# IR_detector_16ch.net
KiCad netlist of a schematic drawn in Altium Designer
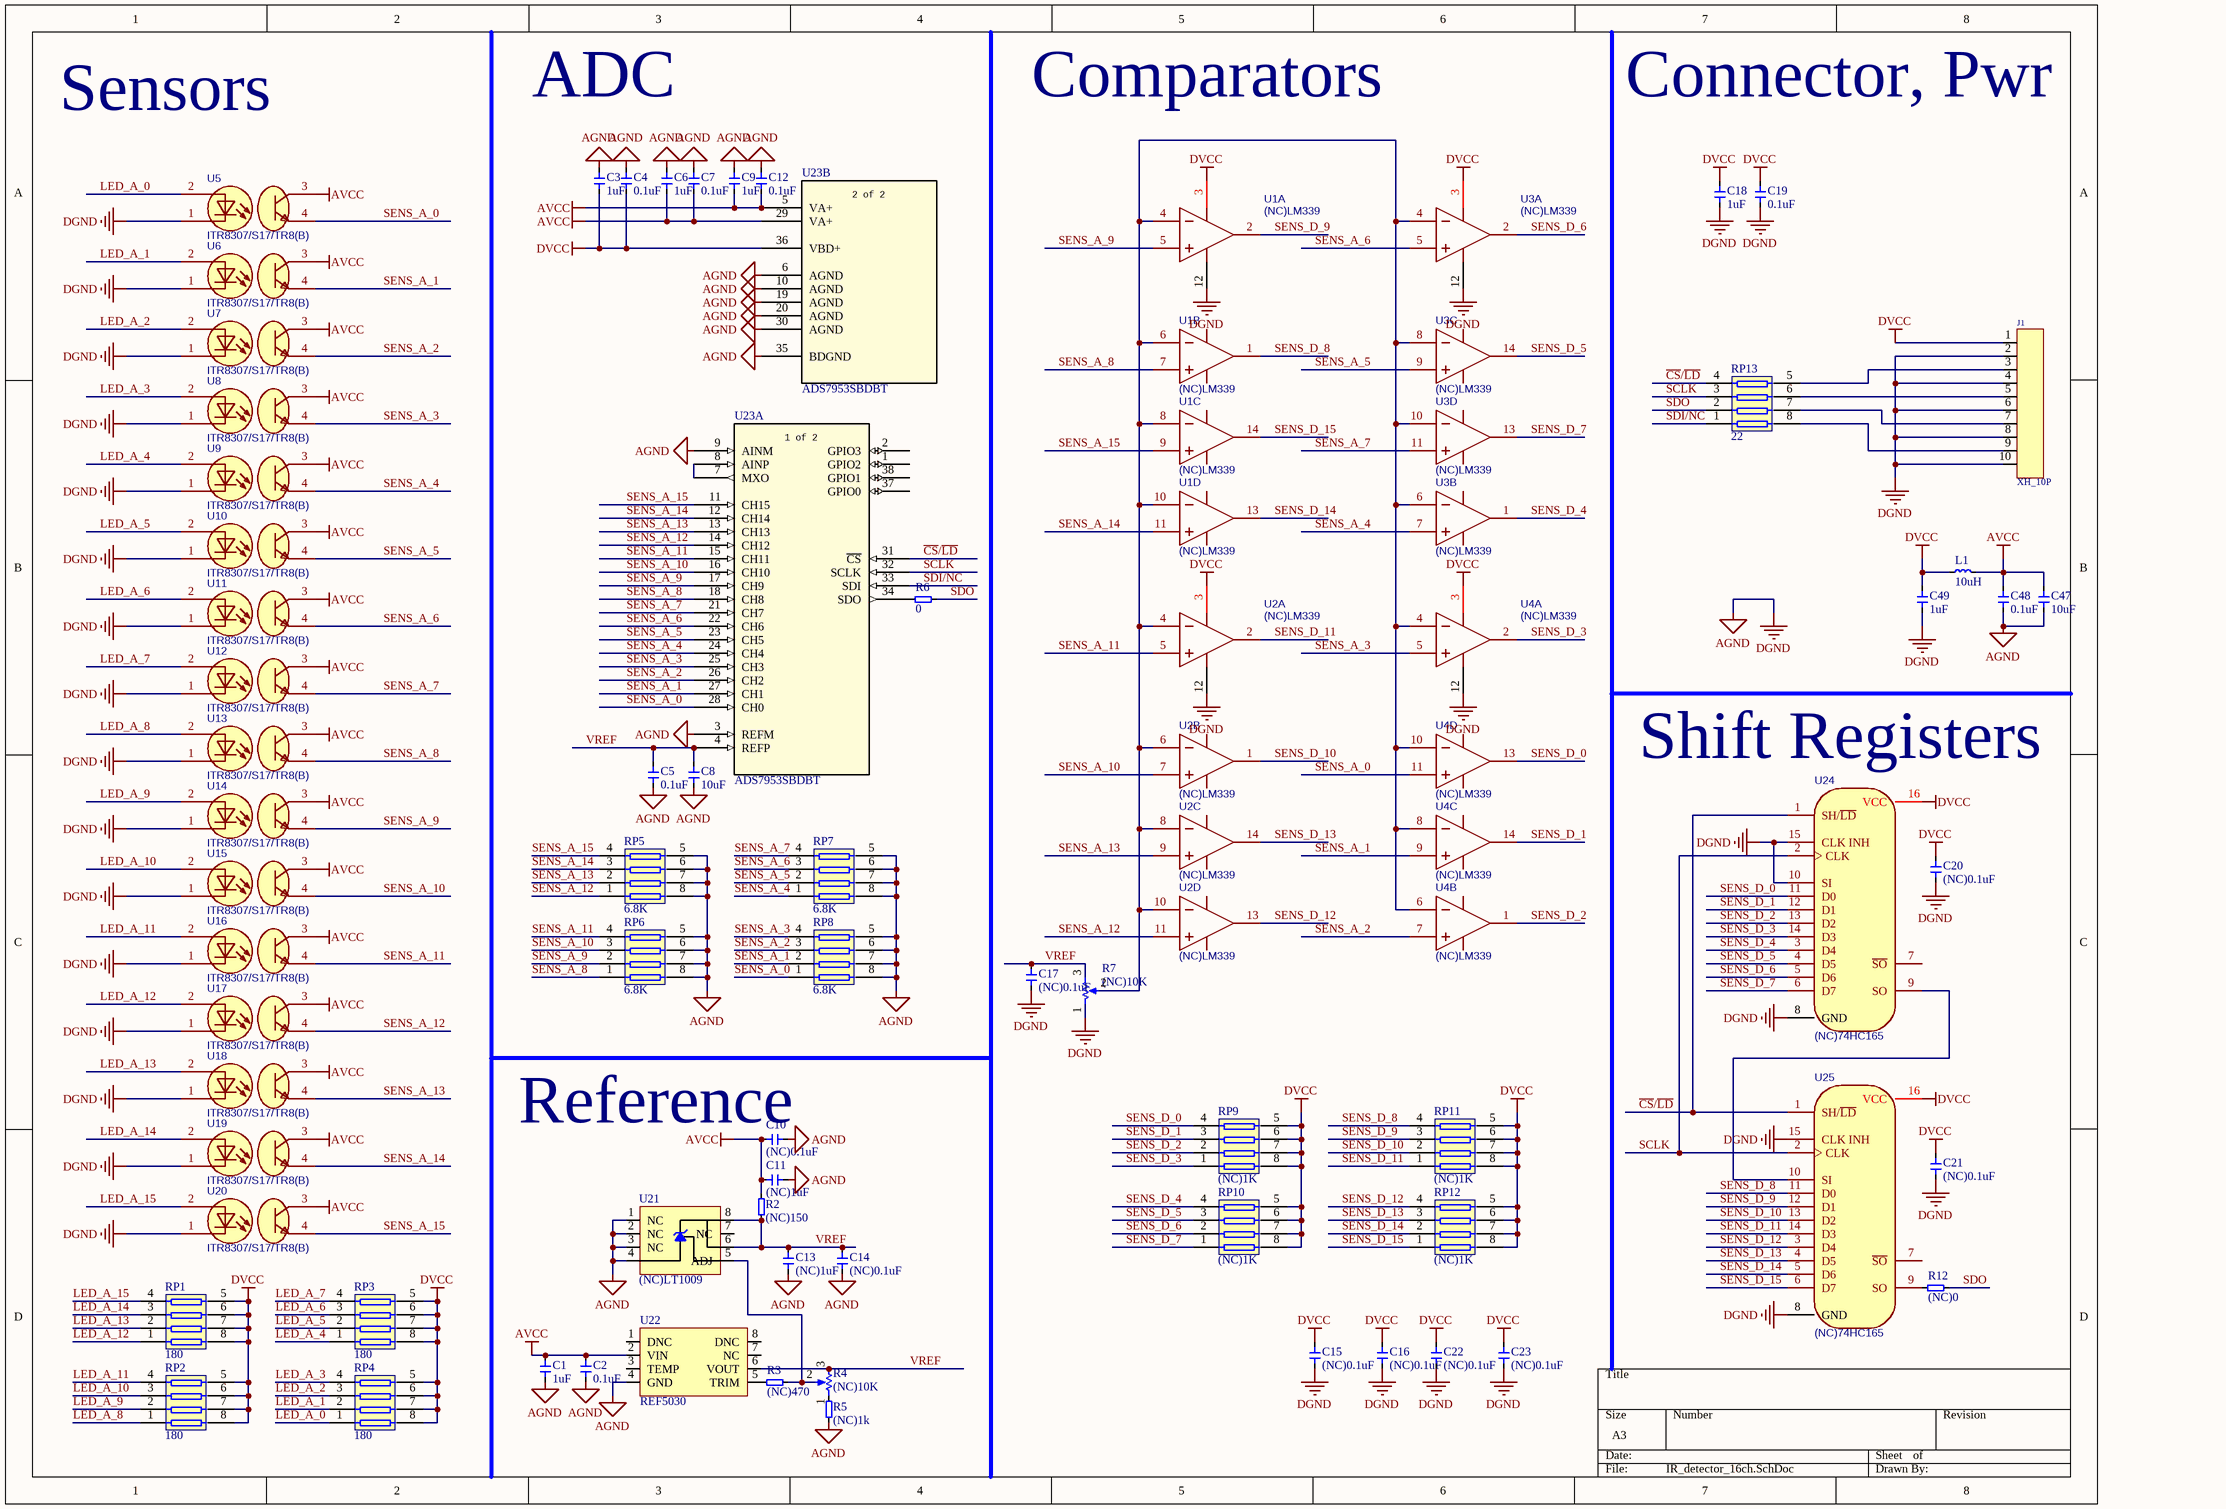
[diagram p0: IR_detector_16ch.SchDoc]

(export (version "E")
  (design (tool "Eeschema 10.0.6"))
  (components
    (comp (ref "C1") (value "1uF") (footprint "0402") (libsource (lib "pants1") (part "Cap")))
    (comp (ref "C2") (value "0.1uF") (footprint "0402") (libsource (lib "pants1") (part "Cap")))
    (comp (ref "C3") (value "1uF") (footprint "0402") (libsource (lib "pants1") (part "Cap")))
    (comp (ref "C4") (value "0.1uF") (footprint "0402") (libsource (lib "pants1") (part "Cap")))
    (comp (ref "C5") (value "0.1uF") (footprint "0402") (libsource (lib "pants1") (part "Cap")))
    (comp (ref "C6") (value "1uF") (footprint "0402") (libsource (lib "pants1") (part "Cap")))
    (comp (ref "C7") (value "0.1uF") (footprint "0402") (libsource (lib "pants1") (part "Cap")))
    (comp (ref "C8") (value "10uF") (footprint "0402") (libsource (lib "pants1") (part "Cap")))
    (comp (ref "C9") (value "1uF") (footprint "0402") (libsource (lib "pants1") (part "Cap")))
    (comp (ref "C10") (value "(NC)0.1uF") (footprint "0402") (libsource (lib "pants1") (part "Cap")))
    (comp (ref "C11") (value "(NC)1uF") (footprint "0402") (libsource (lib "pants1") (part "Cap")))
    (comp (ref "C12") (value "0.1uF") (footprint "0402") (libsource (lib "pants1") (part "Cap")))
    (comp (ref "C13") (value "(NC)1uF") (footprint "0402") (libsource (lib "pants1") (part "Cap")))
    (comp (ref "C14") (value "(NC)0.1uF") (footprint "0402") (libsource (lib "pants1") (part "Cap")))
    (comp (ref "C15") (value "(NC)0.1uF") (footprint "0402") (libsource (lib "pants1") (part "Cap")))
    (comp (ref "C16") (value "(NC)0.1uF") (footprint "0402") (libsource (lib "pants1") (part "Cap")))
    (comp (ref "C17") (value "(NC)0.1uF") (footprint "0402") (libsource (lib "pants1") (part "Cap")))
    (comp (ref "C18") (value "1uF") (footprint "0402") (libsource (lib "pants1") (part "Cap")))
    (comp (ref "C19") (value "0.1uF") (footprint "0402") (libsource (lib "pants1") (part "Cap")))
    (comp (ref "C20") (value "(NC)0.1uF") (footprint "0402") (libsource (lib "pants1") (part "Cap")))
    (comp (ref "C21") (value "(NC)0.1uF") (footprint "0402") (libsource (lib "pants1") (part "Cap")))
    (comp (ref "C22") (value "(NC)0.1uF") (footprint "0402") (libsource (lib "pants1") (part "Cap")))
    (comp (ref "C23") (value "(NC)0.1uF") (footprint "0402") (libsource (lib "pants1") (part "Cap")))
    (comp (ref "C47") (value "10uF") (footprint "0402") (libsource (lib "pants1") (part "Cap")))
    (comp (ref "C48") (value "0.1uF") (footprint "0402") (libsource (lib "pants1") (part "Cap")))
    (comp (ref "C49") (value "1uF") (footprint "0402") (libsource (lib "pants1") (part "Cap")))
    (comp (ref "J1")
      (value "XH_10P")
      (footprint "XH_10P直插弯针")
      (libsource (lib "XH_Connectors") (part "XH_10P"))
    )
    (comp (ref "L1")
      (value "10uH")
      (footprint "0603")
      (description "Inductor")
      (libsource (lib "pants1") (part "Inductor"))
    )
    (comp (ref "R2")
      (value "(NC)150")
      (footprint "0402")
      (description "Resistor")
      (libsource (lib "") (part "Res_1"))
    )
    (comp (ref "R3")
      (value "(NC)470")
      (footprint "0402")
      (description "Resistor")
      (libsource (lib "pants1") (part "Res"))
    )
    (comp (ref "R4") (value "(NC)10K") (footprint "3x3_ResPot") (libsource (lib "pants1") (part "ResPot")))
    (comp (ref "R5")
      (value "(NC)1k")
      (footprint "0402")
      (description "Resistor")
      (libsource (lib "") (part "Res_1"))
    )
    (comp (ref "R6")
      (value "0")
      (footprint "0402")
      (description "Resistor")
      (libsource (lib "pants1") (part "Res"))
    )
    (comp (ref "R7")
      (value "(NC)10K")
      (footprint "3362W-TH_3P-L7.1-W6.9-P2.54-BL-BS")
      (libsource (lib "pants1") (part "ResPot"))
    )
    (comp (ref "R12")
      (value "(NC)0")
      (footprint "0402")
      (description "Resistor")
      (libsource (lib "pants1") (part "Res"))
    )
    (comp (ref "RP1") (value "180") (footprint "8P4R-0603") (libsource (lib "pants1") (part "8P4R_F")))
    (comp (ref "RP2") (value "180") (footprint "8P4R-0603") (libsource (lib "pants1") (part "8P4R_F")))
    (comp (ref "RP3") (value "180") (footprint "8P4R-0603") (libsource (lib "pants1") (part "8P4R_F")))
    (comp (ref "RP4") (value "180") (footprint "8P4R-0603") (libsource (lib "pants1") (part "8P4R_F")))
    (comp (ref "RP5") (value "6.8K") (footprint "8P4R-0603") (libsource (lib "pants1") (part "8P4R_F")))
    (comp (ref "RP6") (value "6.8K") (footprint "8P4R-0603") (libsource (lib "pants1") (part "8P4R_F")))
    (comp (ref "RP7") (value "6.8K") (footprint "8P4R-0603") (libsource (lib "pants1") (part "8P4R_F")))
    (comp (ref "RP8") (value "6.8K") (footprint "8P4R-0603") (libsource (lib "pants1") (part "8P4R_F")))
    (comp (ref "RP9") (value "(NC)1K") (footprint "8P4R-0603") (libsource (lib "pants1") (part "8P4R_F")))
    (comp (ref "RP10") (value "(NC)1K") (footprint "8P4R-0603") (libsource (lib "pants1") (part "8P4R_F")))
    (comp (ref "RP11") (value "(NC)1K") (footprint "8P4R-0603") (libsource (lib "pants1") (part "8P4R_F")))
    (comp (ref "RP12") (value "(NC)1K") (footprint "8P4R-0603") (libsource (lib "pants1") (part "8P4R_F")))
    (comp (ref "RP13") (value "22") (footprint "8P4R-0603") (libsource (lib "pants1") (part "8P4R_F")))
    (comp (ref "U1")
      (value "(NC)LM339")
      (footprint "SOP-14_L8.6-W3.9-P1.27-LS6.0-BL")
      (fields
        (field (name "BOM_SUPPLIER PART") "C431330")
        (field (name "BOM_MANUFACTURER PART") "LM339-SR")
        (field (name "SUBPART_NO") "1")
      )
      (libsource (lib "pants1") (part "LM339"))
    )
    (comp (ref "U2")
      (value "(NC)LM339")
      (footprint "SOP-14_L8.6-W3.9-P1.27-LS6.0-BL")
      (fields
        (field (name "BOM_SUPPLIER PART") "C431330")
        (field (name "BOM_MANUFACTURER PART") "LM339-SR")
        (field (name "SUBPART_NO") "1")
      )
      (libsource (lib "pants1") (part "LM339"))
    )
    (comp (ref "U3")
      (value "(NC)LM339")
      (footprint "SOP-14_L8.6-W3.9-P1.27-LS6.0-BL")
      (fields
        (field (name "BOM_SUPPLIER PART") "C431330")
        (field (name "BOM_MANUFACTURER PART") "LM339-SR")
        (field (name "SUBPART_NO") "1")
      )
      (libsource (lib "pants1") (part "LM339"))
    )
    (comp (ref "U4")
      (value "(NC)LM339")
      (footprint "SOP-14_L8.6-W3.9-P1.27-LS6.0-BL")
      (fields
        (field (name "BOM_SUPPLIER PART") "C431330")
        (field (name "BOM_MANUFACTURER PART") "LM339-SR")
        (field (name "SUBPART_NO") "1")
      )
      (libsource (lib "pants1") (part "LM339"))
    )
    (comp (ref "U5")
      (value "ITR8307/S17/TR8(B)")
      (footprint "OPTO-SMD_ITR8307-S17-TR8-B-TS")
      (fields (field (name "BOM_SUPPLIER PART") "C81632"))
      (libsource (lib "pants1") (part "ITR8307/S17/TR8(B)"))
    )
    (comp (ref "U6")
      (value "ITR8307/S17/TR8(B)")
      (footprint "OPTO-SMD_ITR8307-S17-TR8-B-TS")
      (fields (field (name "BOM_SUPPLIER PART") "C81632"))
      (libsource (lib "pants1") (part "ITR8307/S17/TR8(B)"))
    )
    (comp (ref "U7")
      (value "ITR8307/S17/TR8(B)")
      (footprint "OPTO-SMD_ITR8307-S17-TR8-B-TS")
      (fields (field (name "BOM_SUPPLIER PART") "C81632"))
      (libsource (lib "pants1") (part "ITR8307/S17/TR8(B)"))
    )
    (comp (ref "U8")
      (value "ITR8307/S17/TR8(B)")
      (footprint "OPTO-SMD_ITR8307-S17-TR8-B-TS")
      (fields (field (name "BOM_SUPPLIER PART") "C81632"))
      (libsource (lib "pants1") (part "ITR8307/S17/TR8(B)"))
    )
    (comp (ref "U9")
      (value "ITR8307/S17/TR8(B)")
      (footprint "OPTO-SMD_ITR8307-S17-TR8-B-TS")
      (fields (field (name "BOM_SUPPLIER PART") "C81632"))
      (libsource (lib "pants1") (part "ITR8307/S17/TR8(B)"))
    )
    (comp (ref "U10")
      (value "ITR8307/S17/TR8(B)")
      (footprint "OPTO-SMD_ITR8307-S17-TR8-B-TS")
      (fields (field (name "BOM_SUPPLIER PART") "C81632"))
      (libsource (lib "pants1") (part "ITR8307/S17/TR8(B)"))
    )
    (comp (ref "U11")
      (value "ITR8307/S17/TR8(B)")
      (footprint "OPTO-SMD_ITR8307-S17-TR8-B-TS")
      (fields (field (name "BOM_SUPPLIER PART") "C81632"))
      (libsource (lib "pants1") (part "ITR8307/S17/TR8(B)"))
    )
    (comp (ref "U12")
      (value "ITR8307/S17/TR8(B)")
      (footprint "OPTO-SMD_ITR8307-S17-TR8-B-TS")
      (fields (field (name "BOM_SUPPLIER PART") "C81632"))
      (libsource (lib "pants1") (part "ITR8307/S17/TR8(B)"))
    )
    (comp (ref "U13")
      (value "ITR8307/S17/TR8(B)")
      (footprint "OPTO-SMD_ITR8307-S17-TR8-B-TS")
      (fields (field (name "BOM_SUPPLIER PART") "C81632"))
      (libsource (lib "pants1") (part "ITR8307/S17/TR8(B)"))
    )
    (comp (ref "U14")
      (value "ITR8307/S17/TR8(B)")
      (footprint "OPTO-SMD_ITR8307-S17-TR8-B-TS")
      (fields (field (name "BOM_SUPPLIER PART") "C81632"))
      (libsource (lib "pants1") (part "ITR8307/S17/TR8(B)"))
    )
    (comp (ref "U15")
      (value "ITR8307/S17/TR8(B)")
      (footprint "OPTO-SMD_ITR8307-S17-TR8-B-TS")
      (fields (field (name "BOM_SUPPLIER PART") "C81632"))
      (libsource (lib "pants1") (part "ITR8307/S17/TR8(B)"))
    )
    (comp (ref "U16")
      (value "ITR8307/S17/TR8(B)")
      (footprint "OPTO-SMD_ITR8307-S17-TR8-B-TS")
      (fields (field (name "BOM_SUPPLIER PART") "C81632"))
      (libsource (lib "pants1") (part "ITR8307/S17/TR8(B)"))
    )
    (comp (ref "U17")
      (value "ITR8307/S17/TR8(B)")
      (footprint "OPTO-SMD_ITR8307-S17-TR8-B-TS")
      (fields (field (name "BOM_SUPPLIER PART") "C81632"))
      (libsource (lib "pants1") (part "ITR8307/S17/TR8(B)"))
    )
    (comp (ref "U18")
      (value "ITR8307/S17/TR8(B)")
      (footprint "OPTO-SMD_ITR8307-S17-TR8-B-TS")
      (fields (field (name "BOM_SUPPLIER PART") "C81632"))
      (libsource (lib "pants1") (part "ITR8307/S17/TR8(B)"))
    )
    (comp (ref "U19")
      (value "ITR8307/S17/TR8(B)")
      (footprint "OPTO-SMD_ITR8307-S17-TR8-B-TS")
      (fields (field (name "BOM_SUPPLIER PART") "C81632"))
      (libsource (lib "pants1") (part "ITR8307/S17/TR8(B)"))
    )
    (comp (ref "U20")
      (value "ITR8307/S17/TR8(B)")
      (footprint "OPTO-SMD_ITR8307-S17-TR8-B-TS")
      (fields (field (name "BOM_SUPPLIER PART") "C81632"))
      (libsource (lib "pants1") (part "ITR8307/S17/TR8(B)"))
    )
    (comp (ref "U21")
      (value "(NC)LT1009")
      (footprint "SOP-8_L5.0-W4.0-P1.27-LS6.0-BL")
      (libsource (lib "pants1") (part "LT1009-SOP8"))
    )
    (comp (ref "U22")
      (value "REF5030")
      (footprint "VSSOP-8_L3.0-W3.0-P0.65-LS5.0-BL")
      (libsource (lib "pants1") (part "REF50xx"))
    )
    (comp (ref "U23")
      (value "ADS7953SBDBT")
      (footprint "TSSOP-38_L9.7-W4.4-P0.50-LS6.4-BL")
      (description "12 bit, 1 MSPS, 16 ch, single ended, micro power, sr i/f, SAR ADC")
      (fields
        (field (name "MANUFACTURER") "Texas Instruments")
        (field (name "GENERIC_PART_NUMBER") "ADS7953")
        (field (name "COPYRIGHT") "Copyright (C) 2018 Accelerated Designs. All rights reserved")
      )
      (libsource (lib "pants1") (part "ADS7953SBDBT"))
    )
    (comp (ref "U24")
      (value "(NC)74HC165")
      (footprint "SOP-16_L10.0-W3.9-P1.27-LS6.0-BL")
      (description "8-bit parallel-in/serial-out shift register")
      (libsource (lib "74logic") (part "74_165"))
    )
    (comp (ref "U25")
      (value "(NC)74HC165")
      (footprint "SOP-16_L10.0-W3.9-P1.27-LS6.0-BL")
      (description "8-bit parallel-in/serial-out shift register")
      (libsource (lib "74logic") (part "74_165"))
    )
  )
  (nets
    (net (code "1") (name "/LED_A_0") (class "Default")
      (node (ref "RP4") (pin "1") (pinfunction "1_1") (pintype "passive"))
      (node (ref "U5") (pin "2") (pinfunction "2_2") (pintype "passive"))
    )
    (net (code "2") (name "/LED_A_1") (class "Default")
      (node (ref "RP4") (pin "2") (pinfunction "2_2") (pintype "passive"))
      (node (ref "U6") (pin "2") (pinfunction "2_2") (pintype "passive"))
    )
    (net (code "3") (name "/LED_A_2") (class "Default")
      (node (ref "RP4") (pin "3") (pinfunction "3_3") (pintype "passive"))
      (node (ref "U7") (pin "2") (pinfunction "2_2") (pintype "passive"))
    )
    (net (code "4") (name "/LED_A_3") (class "Default")
      (node (ref "RP4") (pin "4") (pinfunction "4_4") (pintype "passive"))
      (node (ref "U8") (pin "2") (pinfunction "2_2") (pintype "passive"))
    )
    (net (code "5") (name "/LED_A_4") (class "Default")
      (node (ref "RP3") (pin "1") (pinfunction "1_1") (pintype "passive"))
      (node (ref "U9") (pin "2") (pinfunction "2_2") (pintype "passive"))
    )
    (net (code "6") (name "/LED_A_5") (class "Default")
      (node (ref "RP3") (pin "2") (pinfunction "2_2") (pintype "passive"))
      (node (ref "U10") (pin "2") (pinfunction "2_2") (pintype "passive"))
    )
    (net (code "7") (name "/LED_A_6") (class "Default")
      (node (ref "RP3") (pin "3") (pinfunction "3_3") (pintype "passive"))
      (node (ref "U11") (pin "2") (pinfunction "2_2") (pintype "passive"))
    )
    (net (code "8") (name "/LED_A_7") (class "Default")
      (node (ref "RP3") (pin "4") (pinfunction "4_4") (pintype "passive"))
      (node (ref "U12") (pin "2") (pinfunction "2_2") (pintype "passive"))
    )
    (net (code "9") (name "/LED_A_8") (class "Default")
      (node (ref "RP2") (pin "1") (pinfunction "1_1") (pintype "passive"))
      (node (ref "U13") (pin "2") (pinfunction "2_2") (pintype "passive"))
    )
    (net (code "10") (name "/LED_A_9") (class "Default")
      (node (ref "RP2") (pin "2") (pinfunction "2_2") (pintype "passive"))
      (node (ref "U14") (pin "2") (pinfunction "2_2") (pintype "passive"))
    )
    (net (code "11") (name "/LED_A_10") (class "Default")
      (node (ref "RP2") (pin "3") (pinfunction "3_3") (pintype "passive"))
      (node (ref "U15") (pin "2") (pinfunction "2_2") (pintype "passive"))
    )
    (net (code "12") (name "/LED_A_11") (class "Default")
      (node (ref "RP2") (pin "4") (pinfunction "4_4") (pintype "passive"))
      (node (ref "U16") (pin "2") (pinfunction "2_2") (pintype "passive"))
    )
    (net (code "13") (name "/LED_A_12") (class "Default")
      (node (ref "RP1") (pin "1") (pinfunction "1_1") (pintype "passive"))
      (node (ref "U17") (pin "2") (pinfunction "2_2") (pintype "passive"))
    )
    (net (code "14") (name "/LED_A_13") (class "Default")
      (node (ref "RP1") (pin "2") (pinfunction "2_2") (pintype "passive"))
      (node (ref "U18") (pin "2") (pinfunction "2_2") (pintype "passive"))
    )
    (net (code "15") (name "/LED_A_14") (class "Default")
      (node (ref "RP1") (pin "3") (pinfunction "3_3") (pintype "passive"))
      (node (ref "U19") (pin "2") (pinfunction "2_2") (pintype "passive"))
    )
    (net (code "16") (name "/LED_A_15") (class "Default")
      (node (ref "RP1") (pin "4") (pinfunction "4_4") (pintype "passive"))
      (node (ref "U20") (pin "2") (pinfunction "2_2") (pintype "passive"))
    )
    (net (code "17") (name "/SCLK") (class "Default")
      (node (ref "RP13") (pin "3") (pinfunction "3_3") (pintype "passive"))
      (node (ref "U23") (pin "32") (pinfunction "SCLK_32") (pintype "input"))
      (node (ref "U24") (pin "2") (pinfunction "CLK_2") (pintype "passive"))
      (node (ref "U25") (pin "2") (pinfunction "CLK_2") (pintype "passive"))
    )
    (net (code "18") (name "/SDI{slash}NC") (class "Default")
      (node (ref "RP13") (pin "1") (pinfunction "1_1") (pintype "passive"))
      (node (ref "U23") (pin "33") (pinfunction "SDI_33") (pintype "input"))
    )
    (net (code "19") (name "/SDO") (class "Default")
      (node (ref "R12") (pin "2") (pinfunction "2_2") (pintype "passive"))
      (node (ref "R6") (pin "2") (pinfunction "2_2") (pintype "passive"))
      (node (ref "RP13") (pin "2") (pinfunction "2_2") (pintype "passive"))
    )
    (net (code "20") (name "/SENS_A_0") (class "Default")
      (node (ref "RP8") (pin "1") (pinfunction "1_1") (pintype "passive"))
      (node (ref "U23") (pin "28") (pinfunction "CH0_28") (pintype "input"))
      (node (ref "U4") (pin "11") (pinfunction "IN4+_11") (pintype "passive"))
      (node (ref "U5") (pin "4") (pinfunction "4_4") (pintype "passive"))
    )
    (net (code "21") (name "/SENS_A_1") (class "Default")
      (node (ref "RP8") (pin "2") (pinfunction "2_2") (pintype "passive"))
      (node (ref "U23") (pin "27") (pinfunction "CH1_27") (pintype "input"))
      (node (ref "U4") (pin "9") (pinfunction "IN3+_9") (pintype "passive"))
      (node (ref "U6") (pin "4") (pinfunction "4_4") (pintype "passive"))
    )
    (net (code "22") (name "/SENS_A_2") (class "Default")
      (node (ref "RP8") (pin "3") (pinfunction "3_3") (pintype "passive"))
      (node (ref "U23") (pin "26") (pinfunction "CH2_26") (pintype "input"))
      (node (ref "U4") (pin "7") (pinfunction "IN2+_7") (pintype "passive"))
      (node (ref "U7") (pin "4") (pinfunction "4_4") (pintype "passive"))
    )
    (net (code "23") (name "/SENS_A_3") (class "Default")
      (node (ref "RP8") (pin "4") (pinfunction "4_4") (pintype "passive"))
      (node (ref "U23") (pin "25") (pinfunction "CH3_25") (pintype "input"))
      (node (ref "U4") (pin "5") (pinfunction "IN1+_5") (pintype "passive"))
      (node (ref "U8") (pin "4") (pinfunction "4_4") (pintype "passive"))
    )
    (net (code "24") (name "/SENS_A_4") (class "Default")
      (node (ref "RP7") (pin "1") (pinfunction "1_1") (pintype "passive"))
      (node (ref "U23") (pin "24") (pinfunction "CH4_24") (pintype "input"))
      (node (ref "U3") (pin "7") (pinfunction "IN2+_7") (pintype "passive"))
      (node (ref "U9") (pin "4") (pinfunction "4_4") (pintype "passive"))
    )
    (net (code "25") (name "/SENS_A_5") (class "Default")
      (node (ref "RP7") (pin "2") (pinfunction "2_2") (pintype "passive"))
      (node (ref "U10") (pin "4") (pinfunction "4_4") (pintype "passive"))
      (node (ref "U23") (pin "23") (pinfunction "CH5_23") (pintype "input"))
      (node (ref "U3") (pin "9") (pinfunction "IN3+_9") (pintype "passive"))
    )
    (net (code "26") (name "/SENS_A_6") (class "Default")
      (node (ref "RP7") (pin "3") (pinfunction "3_3") (pintype "passive"))
      (node (ref "U11") (pin "4") (pinfunction "4_4") (pintype "passive"))
      (node (ref "U23") (pin "22") (pinfunction "CH6_22") (pintype "input"))
      (node (ref "U3") (pin "5") (pinfunction "IN1+_5") (pintype "passive"))
    )
    (net (code "27") (name "/SENS_A_7") (class "Default")
      (node (ref "RP7") (pin "4") (pinfunction "4_4") (pintype "passive"))
      (node (ref "U12") (pin "4") (pinfunction "4_4") (pintype "passive"))
      (node (ref "U23") (pin "21") (pinfunction "CH7_21") (pintype "input"))
      (node (ref "U3") (pin "11") (pinfunction "IN4+_11") (pintype "passive"))
    )
    (net (code "28") (name "/SENS_A_8") (class "Default")
      (node (ref "RP6") (pin "1") (pinfunction "1_1") (pintype "passive"))
      (node (ref "U1") (pin "7") (pinfunction "IN2+_7") (pintype "passive"))
      (node (ref "U13") (pin "4") (pinfunction "4_4") (pintype "passive"))
      (node (ref "U23") (pin "18") (pinfunction "CH8_18") (pintype "input"))
    )
    (net (code "29") (name "/SENS_A_9") (class "Default")
      (node (ref "RP6") (pin "2") (pinfunction "2_2") (pintype "passive"))
      (node (ref "U1") (pin "5") (pinfunction "IN1+_5") (pintype "passive"))
      (node (ref "U14") (pin "4") (pinfunction "4_4") (pintype "passive"))
      (node (ref "U23") (pin "17") (pinfunction "CH9_17") (pintype "input"))
    )
    (net (code "30") (name "/SENS_A_10") (class "Default")
      (node (ref "RP6") (pin "3") (pinfunction "3_3") (pintype "passive"))
      (node (ref "U15") (pin "4") (pinfunction "4_4") (pintype "passive"))
      (node (ref "U2") (pin "7") (pinfunction "IN2+_7") (pintype "passive"))
      (node (ref "U23") (pin "16") (pinfunction "CH10_16") (pintype "input"))
    )
    (net (code "31") (name "/SENS_A_11") (class "Default")
      (node (ref "RP6") (pin "4") (pinfunction "4_4") (pintype "passive"))
      (node (ref "U16") (pin "4") (pinfunction "4_4") (pintype "passive"))
      (node (ref "U2") (pin "5") (pinfunction "IN1+_5") (pintype "passive"))
      (node (ref "U23") (pin "15") (pinfunction "CH11_15") (pintype "input"))
    )
    (net (code "32") (name "/SENS_A_12") (class "Default")
      (node (ref "RP5") (pin "1") (pinfunction "1_1") (pintype "passive"))
      (node (ref "U17") (pin "4") (pinfunction "4_4") (pintype "passive"))
      (node (ref "U2") (pin "11") (pinfunction "IN4+_11") (pintype "passive"))
      (node (ref "U23") (pin "14") (pinfunction "CH12_14") (pintype "input"))
    )
    (net (code "33") (name "/SENS_A_13") (class "Default")
      (node (ref "RP5") (pin "2") (pinfunction "2_2") (pintype "passive"))
      (node (ref "U18") (pin "4") (pinfunction "4_4") (pintype "passive"))
      (node (ref "U2") (pin "9") (pinfunction "IN3+_9") (pintype "passive"))
      (node (ref "U23") (pin "13") (pinfunction "CH13_13") (pintype "input"))
    )
    (net (code "34") (name "/SENS_A_14") (class "Default")
      (node (ref "RP5") (pin "3") (pinfunction "3_3") (pintype "passive"))
      (node (ref "U1") (pin "11") (pinfunction "IN4+_11") (pintype "passive"))
      (node (ref "U19") (pin "4") (pinfunction "4_4") (pintype "passive"))
      (node (ref "U23") (pin "12") (pinfunction "CH14_12") (pintype "input"))
    )
    (net (code "35") (name "/SENS_A_15") (class "Default")
      (node (ref "RP5") (pin "4") (pinfunction "4_4") (pintype "passive"))
      (node (ref "U1") (pin "9") (pinfunction "IN3+_9") (pintype "passive"))
      (node (ref "U20") (pin "4") (pinfunction "4_4") (pintype "passive"))
      (node (ref "U23") (pin "11") (pinfunction "CH15_11") (pintype "input"))
    )
    (net (code "36") (name "/SENS_D_0") (class "Default")
      (node (ref "RP9") (pin "4") (pinfunction "4_4") (pintype "passive"))
      (node (ref "U24") (pin "11") (pinfunction "D0_11") (pintype "passive"))
      (node (ref "U4") (pin "13") (pinfunction "OUT4_13") (pintype "passive"))
    )
    (net (code "37") (name "/SENS_D_1") (class "Default")
      (node (ref "RP9") (pin "3") (pinfunction "3_3") (pintype "passive"))
      (node (ref "U24") (pin "12") (pinfunction "D1_12") (pintype "passive"))
      (node (ref "U4") (pin "14") (pinfunction "OUT3_14") (pintype "passive"))
    )
    (net (code "38") (name "/SENS_D_2") (class "Default")
      (node (ref "RP9") (pin "2") (pinfunction "2_2") (pintype "passive"))
      (node (ref "U24") (pin "13") (pinfunction "D2_13") (pintype "passive"))
      (node (ref "U4") (pin "1") (pinfunction "OUT2_1") (pintype "passive"))
    )
    (net (code "39") (name "/SENS_D_3") (class "Default")
      (node (ref "RP9") (pin "1") (pinfunction "1_1") (pintype "passive"))
      (node (ref "U24") (pin "14") (pinfunction "D3_14") (pintype "passive"))
      (node (ref "U4") (pin "2") (pinfunction "OUT1_2") (pintype "passive"))
    )
    (net (code "40") (name "/SENS_D_4") (class "Default")
      (node (ref "RP10") (pin "4") (pinfunction "4_4") (pintype "passive"))
      (node (ref "U24") (pin "3") (pinfunction "D4_3") (pintype "passive"))
      (node (ref "U3") (pin "1") (pinfunction "OUT2_1") (pintype "passive"))
    )
    (net (code "41") (name "/SENS_D_5") (class "Default")
      (node (ref "RP10") (pin "3") (pinfunction "3_3") (pintype "passive"))
      (node (ref "U24") (pin "4") (pinfunction "D5_4") (pintype "passive"))
      (node (ref "U3") (pin "14") (pinfunction "OUT3_14") (pintype "passive"))
    )
    (net (code "42") (name "/SENS_D_6") (class "Default")
      (node (ref "RP10") (pin "2") (pinfunction "2_2") (pintype "passive"))
      (node (ref "U24") (pin "5") (pinfunction "D6_5") (pintype "passive"))
      (node (ref "U3") (pin "2") (pinfunction "OUT1_2") (pintype "passive"))
    )
    (net (code "43") (name "/SENS_D_7") (class "Default")
      (node (ref "RP10") (pin "1") (pinfunction "1_1") (pintype "passive"))
      (node (ref "U24") (pin "6") (pinfunction "D7_6") (pintype "passive"))
      (node (ref "U3") (pin "13") (pinfunction "OUT4_13") (pintype "passive"))
    )
    (net (code "44") (name "/SENS_D_8") (class "Default")
      (node (ref "RP11") (pin "4") (pinfunction "4_4") (pintype "passive"))
      (node (ref "U1") (pin "1") (pinfunction "OUT2_1") (pintype "passive"))
      (node (ref "U25") (pin "11") (pinfunction "D0_11") (pintype "passive"))
    )
    (net (code "45") (name "/SENS_D_9") (class "Default")
      (node (ref "RP11") (pin "3") (pinfunction "3_3") (pintype "passive"))
      (node (ref "U1") (pin "2") (pinfunction "OUT1_2") (pintype "passive"))
      (node (ref "U25") (pin "12") (pinfunction "D1_12") (pintype "passive"))
    )
    (net (code "46") (name "/SENS_D_10") (class "Default")
      (node (ref "RP11") (pin "2") (pinfunction "2_2") (pintype "passive"))
      (node (ref "U2") (pin "1") (pinfunction "OUT2_1") (pintype "passive"))
      (node (ref "U25") (pin "13") (pinfunction "D2_13") (pintype "passive"))
    )
    (net (code "47") (name "/SENS_D_11") (class "Default")
      (node (ref "RP11") (pin "1") (pinfunction "1_1") (pintype "passive"))
      (node (ref "U2") (pin "2") (pinfunction "OUT1_2") (pintype "passive"))
      (node (ref "U25") (pin "14") (pinfunction "D3_14") (pintype "passive"))
    )
    (net (code "48") (name "/SENS_D_12") (class "Default")
      (node (ref "RP12") (pin "4") (pinfunction "4_4") (pintype "passive"))
      (node (ref "U2") (pin "13") (pinfunction "OUT4_13") (pintype "passive"))
      (node (ref "U25") (pin "3") (pinfunction "D4_3") (pintype "passive"))
    )
    (net (code "49") (name "/SENS_D_13") (class "Default")
      (node (ref "RP12") (pin "3") (pinfunction "3_3") (pintype "passive"))
      (node (ref "U2") (pin "14") (pinfunction "OUT3_14") (pintype "passive"))
      (node (ref "U25") (pin "4") (pinfunction "D5_4") (pintype "passive"))
    )
    (net (code "50") (name "/SENS_D_14") (class "Default")
      (node (ref "RP12") (pin "2") (pinfunction "2_2") (pintype "passive"))
      (node (ref "U1") (pin "13") (pinfunction "OUT4_13") (pintype "passive"))
      (node (ref "U25") (pin "5") (pinfunction "D6_5") (pintype "passive"))
    )
    (net (code "51") (name "/SENS_D_15") (class "Default")
      (node (ref "RP12") (pin "1") (pinfunction "1_1") (pintype "passive"))
      (node (ref "U1") (pin "14") (pinfunction "OUT3_14") (pintype "passive"))
      (node (ref "U25") (pin "6") (pinfunction "D7_6") (pintype "passive"))
    )
    (net (code "52") (name "/VREF") (class "Default")
      (node (ref "C13") (pin "2") (pinfunction "2_2") (pintype "passive"))
      (node (ref "C14") (pin "2") (pinfunction "2_2") (pintype "passive"))
      (node (ref "C17") (pin "2") (pinfunction "2_2") (pintype "passive"))
      (node (ref "C5") (pin "2") (pinfunction "2_2") (pintype "passive"))
      (node (ref "C8") (pin "2") (pinfunction "2_2") (pintype "passive"))
      (node (ref "R2") (pin "1") (pinfunction "1_1") (pintype "passive"))
      (node (ref "R4") (pin "3") (pintype "passive"))
      (node (ref "R7") (pin "3") (pintype "passive"))
      (node (ref "U21") (pin "6") (pinfunction "K_6") (pintype "passive"))
      (node (ref "U21") (pin "8") (pinfunction "K_8") (pintype "passive"))
      (node (ref "U22") (pin "6") (pinfunction "VOUT_6") (pintype "passive"))
      (node (ref "U23") (pin "4") (pinfunction "REFP_4") (pintype "input"))
    )
    (net (code "53") (name "/~{CS}{slash}~{LD}") (class "Default")
      (node (ref "RP13") (pin "4") (pinfunction "4_4") (pintype "passive"))
      (node (ref "U23") (pin "31") (pinfunction "~{CS}_31") (pintype "input"))
      (node (ref "U24") (pin "1") (pinfunction "SH/~{LD}_1") (pintype "passive"))
      (node (ref "U25") (pin "1") (pinfunction "SH/~{LD}_1") (pintype "passive"))
    )
    (net (code "54") (name "AGND") (class "Default")
      (node (ref "C1") (pin "1") (pinfunction "1_1") (pintype "passive"))
      (node (ref "C10") (pin "1") (pinfunction "1_1") (pintype "passive"))
      (node (ref "C11") (pin "1") (pinfunction "1_1") (pintype "passive"))
      (node (ref "C12") (pin "2") (pinfunction "2_2") (pintype "passive"))
      (node (ref "C13") (pin "1") (pinfunction "1_1") (pintype "passive"))
      (node (ref "C14") (pin "1") (pinfunction "1_1") (pintype "passive"))
      (node (ref "C15") (pin "1") (pinfunction "1_1") (pintype "passive"))
      (node (ref "C16") (pin "1") (pinfunction "1_1") (pintype "passive"))
      (node (ref "C17") (pin "1") (pinfunction "1_1") (pintype "passive"))
      (node (ref "C18") (pin "1") (pinfunction "1_1") (pintype "passive"))
      (node (ref "C19") (pin "1") (pinfunction "1_1") (pintype "passive"))
      (node (ref "C2") (pin "1") (pinfunction "1_1") (pintype "passive"))
      (node (ref "C20") (pin "1") (pinfunction "1_1") (pintype "passive"))
      (node (ref "C21") (pin "1") (pinfunction "1_1") (pintype "passive"))
      (node (ref "C22") (pin "1") (pinfunction "1_1") (pintype "passive"))
      (node (ref "C23") (pin "1") (pinfunction "1_1") (pintype "passive"))
      (node (ref "C3") (pin "2") (pinfunction "2_2") (pintype "passive"))
      (node (ref "C4") (pin "2") (pinfunction "2_2") (pintype "passive"))
      (node (ref "C47") (pin "1") (pinfunction "1_1") (pintype "passive"))
      (node (ref "C48") (pin "1") (pinfunction "1_1") (pintype "passive"))
      (node (ref "C49") (pin "1") (pinfunction "1_1") (pintype "passive"))
      (node (ref "C5") (pin "1") (pinfunction "1_1") (pintype "passive"))
      (node (ref "C6") (pin "2") (pinfunction "2_2") (pintype "passive"))
      (node (ref "C7") (pin "2") (pinfunction "2_2") (pintype "passive"))
      (node (ref "C8") (pin "1") (pinfunction "1_1") (pintype "passive"))
      (node (ref "C9") (pin "2") (pinfunction "2_2") (pintype "passive"))
      (node (ref "J1") (pin "10") (pinfunction "10_10") (pintype "passive"))
      (node (ref "J1") (pin "2") (pinfunction "2_2") (pintype "passive"))
      (node (ref "J1") (pin "4") (pinfunction "4_4") (pintype "passive"))
      (node (ref "J1") (pin "6") (pinfunction "6_6") (pintype "passive"))
      (node (ref "J1") (pin "8") (pinfunction "8_8") (pintype "passive"))
      (node (ref "R5") (pin "1") (pinfunction "1_1") (pintype "passive"))
      (node (ref "R7") (pin "1") (pintype "passive"))
      (node (ref "RP5") (pin "5") (pinfunction "5_5") (pintype "passive"))
      (node (ref "RP5") (pin "6") (pinfunction "6_6") (pintype "passive"))
      (node (ref "RP5") (pin "7") (pinfunction "7_7") (pintype "passive"))
      (node (ref "RP5") (pin "8") (pinfunction "8_8") (pintype "passive"))
      (node (ref "RP6") (pin "5") (pinfunction "5_5") (pintype "passive"))
      (node (ref "RP6") (pin "6") (pinfunction "6_6") (pintype "passive"))
      (node (ref "RP6") (pin "7") (pinfunction "7_7") (pintype "passive"))
      (node (ref "RP6") (pin "8") (pinfunction "8_8") (pintype "passive"))
      (node (ref "RP7") (pin "5") (pinfunction "5_5") (pintype "passive"))
      (node (ref "RP7") (pin "6") (pinfunction "6_6") (pintype "passive"))
      (node (ref "RP7") (pin "7") (pinfunction "7_7") (pintype "passive"))
      (node (ref "RP7") (pin "8") (pinfunction "8_8") (pintype "passive"))
      (node (ref "RP8") (pin "5") (pinfunction "5_5") (pintype "passive"))
      (node (ref "RP8") (pin "6") (pinfunction "6_6") (pintype "passive"))
      (node (ref "RP8") (pin "7") (pinfunction "7_7") (pintype "passive"))
      (node (ref "RP8") (pin "8") (pinfunction "8_8") (pintype "passive"))
      (node (ref "U1") (pin "12") (pinfunction "GND_12") (pintype "passive"))
      (node (ref "U10") (pin "1") (pinfunction "1_1") (pintype "passive"))
      (node (ref "U11") (pin "1") (pinfunction "1_1") (pintype "passive"))
      (node (ref "U12") (pin "1") (pinfunction "1_1") (pintype "passive"))
      (node (ref "U13") (pin "1") (pinfunction "1_1") (pintype "passive"))
      (node (ref "U14") (pin "1") (pinfunction "1_1") (pintype "passive"))
      (node (ref "U15") (pin "1") (pinfunction "1_1") (pintype "passive"))
      (node (ref "U16") (pin "1") (pinfunction "1_1") (pintype "passive"))
      (node (ref "U17") (pin "1") (pinfunction "1_1") (pintype "passive"))
      (node (ref "U18") (pin "1") (pinfunction "1_1") (pintype "passive"))
      (node (ref "U19") (pin "1") (pinfunction "1_1") (pintype "passive"))
      (node (ref "U2") (pin "12") (pinfunction "GND_12") (pintype "passive"))
      (node (ref "U20") (pin "1") (pinfunction "1_1") (pintype "passive"))
      (node (ref "U21") (pin "1") (pinfunction "NC_1") (pintype "passive"))
      (node (ref "U21") (pin "2") (pinfunction "NC_2") (pintype "passive"))
      (node (ref "U21") (pin "3") (pinfunction "NC_3") (pintype "passive"))
      (node (ref "U21") (pin "4") (pinfunction "A_4") (pintype "passive"))
      (node (ref "U22") (pin "4") (pinfunction "GND_4") (pintype "passive"))
      (node (ref "U23") (pin "10") (pinfunction "AGND_10") (pintype "power_in"))
      (node (ref "U23") (pin "19") (pinfunction "AGND_19") (pintype "power_in"))
      (node (ref "U23") (pin "20") (pinfunction "AGND_20") (pintype "power_in"))
      (node (ref "U23") (pin "3") (pinfunction "REFM_3") (pintype "input"))
      (node (ref "U23") (pin "30") (pinfunction "AGND_30") (pintype "power_in"))
      (node (ref "U23") (pin "35") (pinfunction "BDGND_35") (pintype "power_in"))
      (node (ref "U23") (pin "6") (pinfunction "AGND_6") (pintype "power_in"))
      (node (ref "U23") (pin "9") (pinfunction "AINM_9") (pintype "input"))
      (node (ref "U24") (pin "10") (pinfunction "SI_10") (pintype "passive"))
      (node (ref "U24") (pin "15") (pinfunction "CLK_INH_15") (pintype "passive"))
      (node (ref "U24") (pin "8") (pinfunction "GND_8") (pintype "passive"))
      (node (ref "U25") (pin "15") (pinfunction "CLK_INH_15") (pintype "passive"))
      (node (ref "U25") (pin "8") (pinfunction "GND_8") (pintype "passive"))
      (node (ref "U3") (pin "12") (pinfunction "GND_12") (pintype "passive"))
      (node (ref "U4") (pin "12") (pinfunction "GND_12") (pintype "passive"))
      (node (ref "U5") (pin "1") (pinfunction "1_1") (pintype "passive"))
      (node (ref "U6") (pin "1") (pinfunction "1_1") (pintype "passive"))
      (node (ref "U7") (pin "1") (pinfunction "1_1") (pintype "passive"))
      (node (ref "U8") (pin "1") (pinfunction "1_1") (pintype "passive"))
      (node (ref "U9") (pin "1") (pinfunction "1_1") (pintype "passive"))
    )
    (net (code "55") (name "AVCC") (class "Default")
      (node (ref "C1") (pin "2") (pinfunction "2_2") (pintype "passive"))
      (node (ref "C10") (pin "2") (pinfunction "2_2") (pintype "passive"))
      (node (ref "C11") (pin "2") (pinfunction "2_2") (pintype "passive"))
      (node (ref "C12") (pin "1") (pinfunction "1_1") (pintype "passive"))
      (node (ref "C2") (pin "2") (pinfunction "2_2") (pintype "passive"))
      (node (ref "C47") (pin "2") (pinfunction "2_2") (pintype "passive"))
      (node (ref "C48") (pin "2") (pinfunction "2_2") (pintype "passive"))
      (node (ref "C6") (pin "1") (pinfunction "1_1") (pintype "passive"))
      (node (ref "C7") (pin "1") (pinfunction "1_1") (pintype "passive"))
      (node (ref "C9") (pin "1") (pinfunction "1_1") (pintype "passive"))
      (node (ref "L1") (pin "2") (pinfunction "2_2") (pintype "passive"))
      (node (ref "R2") (pin "2") (pinfunction "2_2") (pintype "passive"))
      (node (ref "U10") (pin "3") (pinfunction "3_3") (pintype "passive"))
      (node (ref "U11") (pin "3") (pinfunction "3_3") (pintype "passive"))
      (node (ref "U12") (pin "3") (pinfunction "3_3") (pintype "passive"))
      (node (ref "U13") (pin "3") (pinfunction "3_3") (pintype "passive"))
      (node (ref "U14") (pin "3") (pinfunction "3_3") (pintype "passive"))
      (node (ref "U15") (pin "3") (pinfunction "3_3") (pintype "passive"))
      (node (ref "U16") (pin "3") (pinfunction "3_3") (pintype "passive"))
      (node (ref "U17") (pin "3") (pinfunction "3_3") (pintype "passive"))
      (node (ref "U18") (pin "3") (pinfunction "3_3") (pintype "passive"))
      (node (ref "U19") (pin "3") (pinfunction "3_3") (pintype "passive"))
      (node (ref "U20") (pin "3") (pinfunction "3_3") (pintype "passive"))
      (node (ref "U22") (pin "2") (pinfunction "VIN_2") (pintype "passive"))
      (node (ref "U23") (pin "29") (pinfunction "VA+_29") (pintype "power_in"))
      (node (ref "U23") (pin "5") (pinfunction "VA+_5") (pintype "power_in"))
      (node (ref "U5") (pin "3") (pinfunction "3_3") (pintype "passive"))
      (node (ref "U6") (pin "3") (pinfunction "3_3") (pintype "passive"))
      (node (ref "U7") (pin "3") (pinfunction "3_3") (pintype "passive"))
      (node (ref "U8") (pin "3") (pinfunction "3_3") (pintype "passive"))
      (node (ref "U9") (pin "3") (pinfunction "3_3") (pintype "passive"))
    )
    (net (code "56") (name "DVCC") (class "Default")
      (node (ref "C15") (pin "2") (pinfunction "2_2") (pintype "passive"))
      (node (ref "C16") (pin "2") (pinfunction "2_2") (pintype "passive"))
      (node (ref "C18") (pin "2") (pinfunction "2_2") (pintype "passive"))
      (node (ref "C19") (pin "2") (pinfunction "2_2") (pintype "passive"))
      (node (ref "C20") (pin "2") (pinfunction "2_2") (pintype "passive"))
      (node (ref "C21") (pin "2") (pinfunction "2_2") (pintype "passive"))
      (node (ref "C22") (pin "2") (pinfunction "2_2") (pintype "passive"))
      (node (ref "C23") (pin "2") (pinfunction "2_2") (pintype "passive"))
      (node (ref "C3") (pin "1") (pinfunction "1_1") (pintype "passive"))
      (node (ref "C4") (pin "1") (pinfunction "1_1") (pintype "passive"))
      (node (ref "C49") (pin "2") (pinfunction "2_2") (pintype "passive"))
      (node (ref "J1") (pin "1") (pinfunction "1_1") (pintype "passive"))
      (node (ref "L1") (pin "1") (pinfunction "1_1") (pintype "passive"))
      (node (ref "RP1") (pin "5") (pinfunction "5_5") (pintype "passive"))
      (node (ref "RP1") (pin "6") (pinfunction "6_6") (pintype "passive"))
      (node (ref "RP1") (pin "7") (pinfunction "7_7") (pintype "passive"))
      (node (ref "RP1") (pin "8") (pinfunction "8_8") (pintype "passive"))
      (node (ref "RP10") (pin "5") (pinfunction "5_5") (pintype "passive"))
      (node (ref "RP10") (pin "6") (pinfunction "6_6") (pintype "passive"))
      (node (ref "RP10") (pin "7") (pinfunction "7_7") (pintype "passive"))
      (node (ref "RP10") (pin "8") (pinfunction "8_8") (pintype "passive"))
      (node (ref "RP11") (pin "5") (pinfunction "5_5") (pintype "passive"))
      (node (ref "RP11") (pin "6") (pinfunction "6_6") (pintype "passive"))
      (node (ref "RP11") (pin "7") (pinfunction "7_7") (pintype "passive"))
      (node (ref "RP11") (pin "8") (pinfunction "8_8") (pintype "passive"))
      (node (ref "RP12") (pin "5") (pinfunction "5_5") (pintype "passive"))
      (node (ref "RP12") (pin "6") (pinfunction "6_6") (pintype "passive"))
      (node (ref "RP12") (pin "7") (pinfunction "7_7") (pintype "passive"))
      (node (ref "RP12") (pin "8") (pinfunction "8_8") (pintype "passive"))
      (node (ref "RP2") (pin "5") (pinfunction "5_5") (pintype "passive"))
      (node (ref "RP2") (pin "6") (pinfunction "6_6") (pintype "passive"))
      (node (ref "RP2") (pin "7") (pinfunction "7_7") (pintype "passive"))
      (node (ref "RP2") (pin "8") (pinfunction "8_8") (pintype "passive"))
      (node (ref "RP3") (pin "5") (pinfunction "5_5") (pintype "passive"))
      (node (ref "RP3") (pin "6") (pinfunction "6_6") (pintype "passive"))
      (node (ref "RP3") (pin "7") (pinfunction "7_7") (pintype "passive"))
      (node (ref "RP3") (pin "8") (pinfunction "8_8") (pintype "passive"))
      (node (ref "RP4") (pin "5") (pinfunction "5_5") (pintype "passive"))
      (node (ref "RP4") (pin "6") (pinfunction "6_6") (pintype "passive"))
      (node (ref "RP4") (pin "7") (pinfunction "7_7") (pintype "passive"))
      (node (ref "RP4") (pin "8") (pinfunction "8_8") (pintype "passive"))
      (node (ref "RP9") (pin "5") (pinfunction "5_5") (pintype "passive"))
      (node (ref "RP9") (pin "6") (pinfunction "6_6") (pintype "passive"))
      (node (ref "RP9") (pin "7") (pinfunction "7_7") (pintype "passive"))
      (node (ref "RP9") (pin "8") (pinfunction "8_8") (pintype "passive"))
      (node (ref "U1") (pin "3") (pinfunction "VCC_3") (pintype "passive"))
      (node (ref "U2") (pin "3") (pinfunction "VCC_3") (pintype "passive"))
      (node (ref "U23") (pin "36") (pinfunction "VBD+_36") (pintype "power_in"))
      (node (ref "U24") (pin "16") (pinfunction "VCC_16") (pintype "passive"))
      (node (ref "U25") (pin "16") (pinfunction "VCC_16") (pintype "passive"))
      (node (ref "U3") (pin "3") (pinfunction "VCC_3") (pintype "passive"))
      (node (ref "U4") (pin "3") (pinfunction "VCC_3") (pintype "passive"))
    )
    (net (code "57") (name "Net-(J1-Pad3)") (class "Default")
      (node (ref "J1") (pin "3") (pinfunction "3_3") (pintype "passive"))
      (node (ref "RP13") (pin "5") (pinfunction "5_5") (pintype "passive"))
    )
    (net (code "58") (name "Net-(J1-Pad5)") (class "Default")
      (node (ref "J1") (pin "5") (pinfunction "5_5") (pintype "passive"))
      (node (ref "RP13") (pin "6") (pinfunction "6_6") (pintype "passive"))
    )
    (net (code "59") (name "Net-(J1-Pad7)") (class "Default")
      (node (ref "J1") (pin "7") (pinfunction "7_7") (pintype "passive"))
      (node (ref "RP13") (pin "7") (pinfunction "7_7") (pintype "passive"))
    )
    (net (code "60") (name "Net-(J1-Pad9)") (class "Default")
      (node (ref "J1") (pin "9") (pinfunction "9_9") (pintype "passive"))
      (node (ref "RP13") (pin "8") (pinfunction "8_8") (pintype "passive"))
    )
    (net (code "61") (name "Net-(R4-Pad1)") (class "Default")
      (node (ref "R4") (pin "1") (pintype "passive"))
      (node (ref "R5") (pin "2") (pinfunction "2_2") (pintype "passive"))
    )
    (net (code "62") (name "Net-(U1A-IN1-)") (class "Default")
      (node (ref "R7") (pin "2") (pintype "passive"))
      (node (ref "U1") (pin "10") (pinfunction "IN4-_10") (pintype "passive"))
      (node (ref "U1") (pin "4") (pinfunction "IN1-_4") (pintype "passive"))
      (node (ref "U1") (pin "6") (pinfunction "IN2-_6") (pintype "passive"))
      (node (ref "U1") (pin "8") (pinfunction "IN3-_8") (pintype "passive"))
      (node (ref "U2") (pin "10") (pinfunction "IN4-_10") (pintype "passive"))
      (node (ref "U2") (pin "4") (pinfunction "IN1-_4") (pintype "passive"))
      (node (ref "U2") (pin "6") (pinfunction "IN2-_6") (pintype "passive"))
      (node (ref "U2") (pin "8") (pinfunction "IN3-_8") (pintype "passive"))
      (node (ref "U3") (pin "10") (pinfunction "IN4-_10") (pintype "passive"))
      (node (ref "U3") (pin "4") (pinfunction "IN1-_4") (pintype "passive"))
      (node (ref "U3") (pin "6") (pinfunction "IN2-_6") (pintype "passive"))
      (node (ref "U3") (pin "8") (pinfunction "IN3-_8") (pintype "passive"))
      (node (ref "U4") (pin "10") (pinfunction "IN4-_10") (pintype "passive"))
      (node (ref "U4") (pin "4") (pinfunction "IN1-_4") (pintype "passive"))
      (node (ref "U4") (pin "6") (pinfunction "IN2-_6") (pintype "passive"))
      (node (ref "U4") (pin "8") (pinfunction "IN3-_8") (pintype "passive"))
    )
    (net (code "63") (name "Net-(U21-ADJ)") (class "Default")
      (node (ref "R3") (pin "2") (pinfunction "2_2") (pintype "passive"))
      (node (ref "R4") (pin "2") (pintype "passive"))
      (node (ref "U21") (pin "5") (pinfunction "ADJ_5") (pintype "passive"))
    )
    (net (code "64") (name "Net-(U22-TRIM)") (class "Default")
      (node (ref "R3") (pin "1") (pinfunction "1_1") (pintype "passive"))
      (node (ref "U22") (pin "5") (pinfunction "TRIM_5") (pintype "passive"))
    )
    (net (code "65") (name "Net-(U23A-AINP)") (class "Default")
      (node (ref "U23") (pin "7") (pinfunction "MXO_7") (pintype "output"))
      (node (ref "U23") (pin "8") (pinfunction "AINP_8") (pintype "input"))
    )
    (net (code "66") (name "Net-(U23A-SDO)") (class "Default")
      (node (ref "R6") (pin "1") (pinfunction "1_1") (pintype "passive"))
      (node (ref "U23") (pin "34") (pinfunction "SDO_34") (pintype "output"))
    )
    (net (code "67") (name "Net-(U24-SO)") (class "Default")
      (node (ref "U24") (pin "9") (pinfunction "SO_9") (pintype "passive"))
      (node (ref "U25") (pin "10") (pinfunction "SI_10") (pintype "passive"))
    )
    (net (code "68") (name "Net-(U25-SO)") (class "Default")
      (node (ref "R12") (pin "1") (pinfunction "1_1") (pintype "passive"))
      (node (ref "U25") (pin "9") (pinfunction "SO_9") (pintype "passive"))
    )
    (net (code "69") (name "unconnected-(U21-NC-Pad7)") (class "Default")
      (node (ref "U21") (pin "7") (pinfunction "NC_7") (pintype "passive"))
    )
    (net (code "70") (name "unconnected-(U22-DNC-Pad1)") (class "Default")
      (node (ref "U22") (pin "1") (pinfunction "DNC_1") (pintype "passive"))
    )
    (net (code "71") (name "unconnected-(U22-DNC-Pad8)") (class "Default")
      (node (ref "U22") (pin "8") (pinfunction "DNC_8") (pintype "passive"))
    )
    (net (code "72") (name "unconnected-(U22-NC-Pad7)") (class "Default")
      (node (ref "U22") (pin "7") (pinfunction "NC_7") (pintype "passive"))
    )
    (net (code "73") (name "unconnected-(U22-TEMP-Pad3)") (class "Default")
      (node (ref "U22") (pin "3") (pinfunction "TEMP_3") (pintype "passive"))
    )
    (net (code "74") (name "unconnected-(U23A-GPIO0-Pad37)") (class "Default")
      (node (ref "U23") (pin "37") (pinfunction "GPIO0_37") (pintype "bidirectional"))
    )
    (net (code "75") (name "unconnected-(U23A-GPIO1-Pad38)") (class "Default")
      (node (ref "U23") (pin "38") (pinfunction "GPIO1_38") (pintype "bidirectional"))
    )
    (net (code "76") (name "unconnected-(U23A-GPIO2-Pad1)") (class "Default")
      (node (ref "U23") (pin "1") (pinfunction "GPIO2_1") (pintype "bidirectional"))
    )
    (net (code "77") (name "unconnected-(U23A-GPIO3-Pad2)") (class "Default")
      (node (ref "U23") (pin "2") (pinfunction "GPIO3_2") (pintype "bidirectional"))
    )
    (net (code "78") (name "unconnected-(U24-~{SO}-Pad7)") (class "Default")
      (node (ref "U24") (pin "7") (pinfunction "~{SO}_7") (pintype "passive"))
    )
    (net (code "79") (name "unconnected-(U25-~{SO}-Pad7)") (class "Default")
      (node (ref "U25") (pin "7") (pinfunction "~{SO}_7") (pintype "passive"))
    )
  )
)
